# XBee-NewRoute.net
KiCad netlist of a schematic drawn in EAGLE
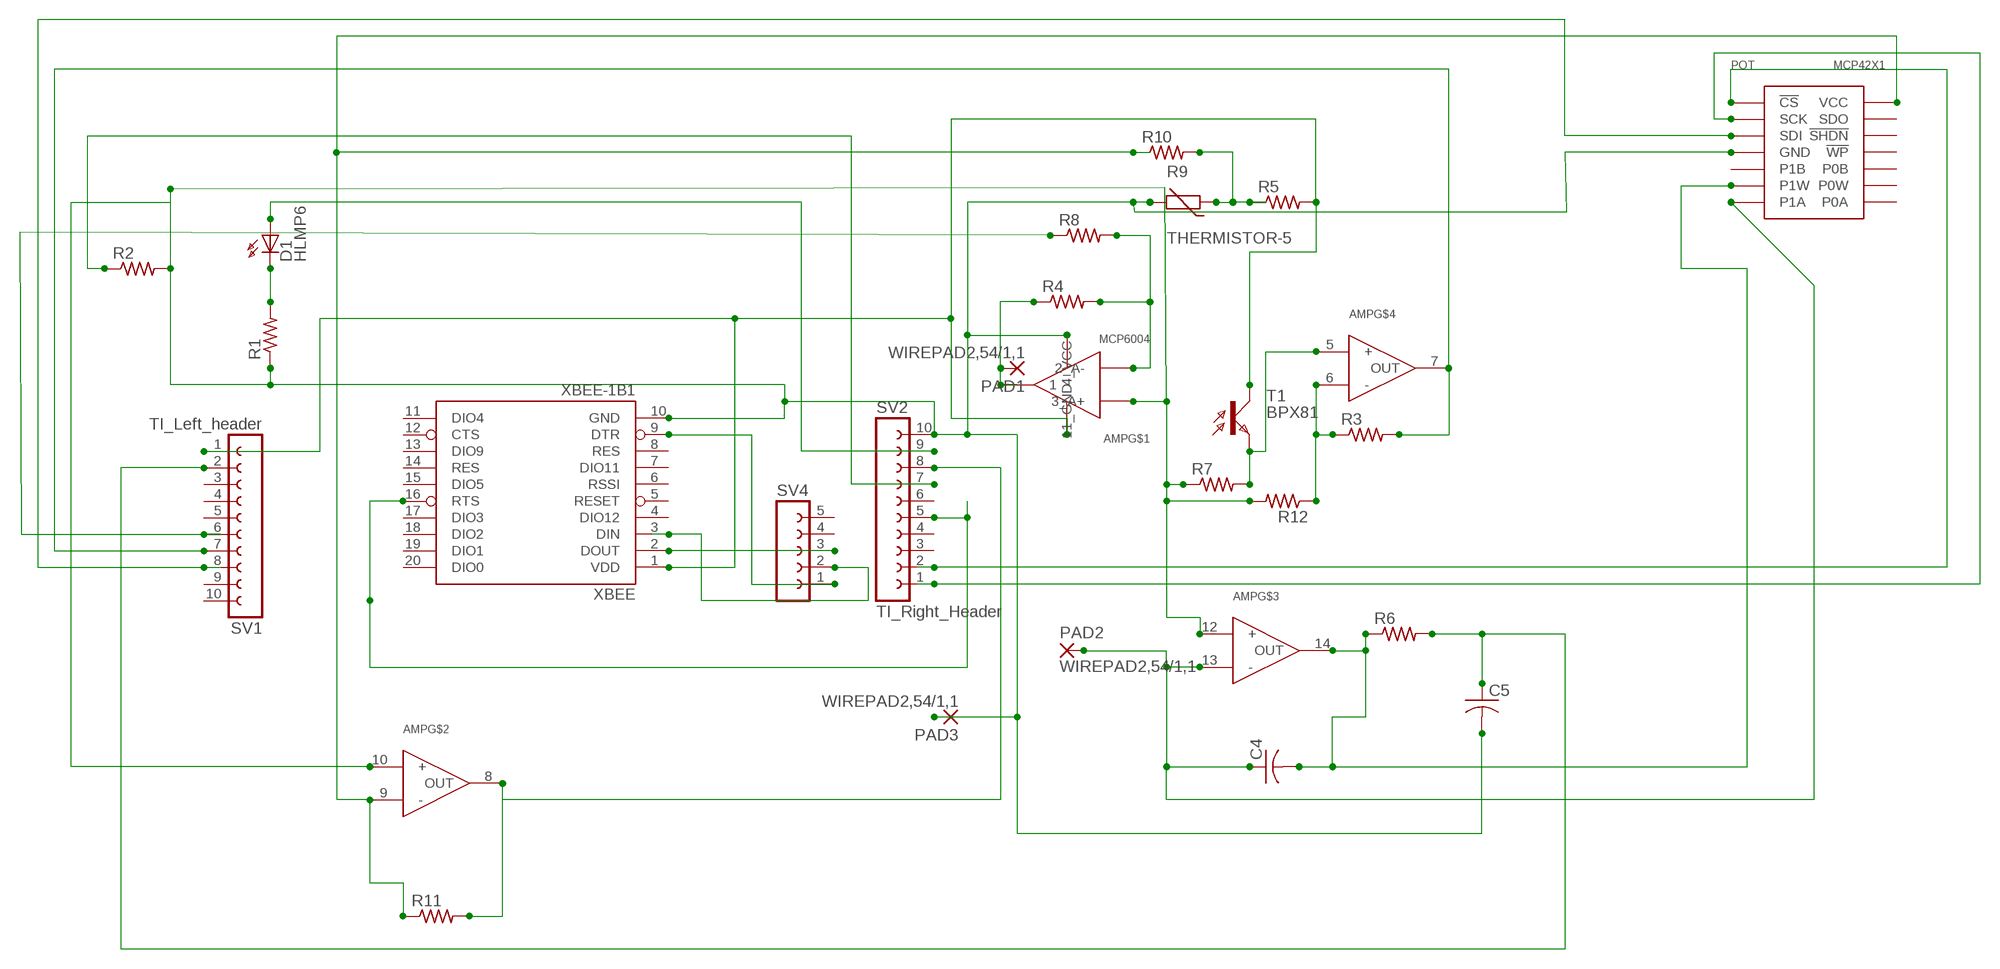
[diagram p0: schematic, sheet 1]

(export (version "E")
  (design (tool "Eeschema 10.0.6"))
  (components
    (comp (ref "AMP")
      (value "MCP6004")
      (footprint "eagle-import:SO014")
      (libsource (lib "eagle-import") (part "MCP6004"))
    )
    (comp (ref "C4")
      (value "C-USC0603")
      (footprint "eagle-import:C0603")
      (libsource (lib "eagle-import") (part "C-USC0603"))
    )
    (comp (ref "C5")
      (value "C-USC0603")
      (footprint "eagle-import:C0603")
      (libsource (lib "eagle-import") (part "C-USC0603"))
    )
    (comp (ref "D1")
      (value "HLMP6")
      (footprint "eagle-import:HLMP6")
      (fields (field (name "MF") "AGILENT TECHNOLOGIES") (field (name "MPN") "HLMP-6500"))
      (libsource (lib "eagle-import") (part "HLMP6"))
    )
    (comp (ref "PAD1")
      (value "WIREPAD2,54/1,1")
      (footprint "eagle-import:2,54_1,1")
      (libsource (lib "eagle-import") (part "WIREPAD2,54/1,1"))
    )
    (comp (ref "PAD2")
      (value "WIREPAD2,54/1,1")
      (footprint "eagle-import:2,54_1,1")
      (libsource (lib "eagle-import") (part "WIREPAD2,54/1,1"))
    )
    (comp (ref "PAD3")
      (value "WIREPAD2,54/1,1")
      (footprint "eagle-import:2,54_1,1")
      (libsource (lib "eagle-import") (part "WIREPAD2,54/1,1"))
    )
    (comp (ref "POT")
      (value "MCP42X1")
      (footprint "eagle-import:SO014")
      (libsource (lib "eagle-import") (part "MCP42X1_DIGITAL_POTSO014"))
    )
    (comp (ref "R1")
      (value "R-US_R0603")
      (footprint "eagle-import:R0603")
      (libsource (lib "eagle-import") (part "R-US_R0603"))
    )
    (comp (ref "R2")
      (value "R-US_R0603")
      (footprint "eagle-import:R0603")
      (libsource (lib "eagle-import") (part "R-US_R0603"))
    )
    (comp (ref "R3")
      (value "R-US_R0603")
      (footprint "eagle-import:R0603")
      (libsource (lib "eagle-import") (part "R-US_R0603"))
    )
    (comp (ref "R4")
      (value "R-US_R0603")
      (footprint "eagle-import:R0603")
      (libsource (lib "eagle-import") (part "R-US_R0603"))
    )
    (comp (ref "R5")
      (value "R-US_R0603")
      (footprint "eagle-import:R0603")
      (libsource (lib "eagle-import") (part "R-US_R0603"))
    )
    (comp (ref "R6")
      (value "R-US_R0603")
      (footprint "eagle-import:R0603")
      (libsource (lib "eagle-import") (part "R-US_R0603"))
    )
    (comp (ref "R7")
      (value "R-US_R0603")
      (footprint "eagle-import:R0603")
      (libsource (lib "eagle-import") (part "R-US_R0603"))
    )
    (comp (ref "R8")
      (value "R-US_R0603")
      (footprint "eagle-import:R0603")
      (libsource (lib "eagle-import") (part "R-US_R0603"))
    )
    (comp (ref "R9")
      (value "THERMISTOR-5")
      (footprint "eagle-import:R-5")
      (libsource (lib "eagle-import") (part "THERMISTOR-5"))
    )
    (comp (ref "R10")
      (value "R-US_R0603")
      (footprint "eagle-import:R0603")
      (libsource (lib "eagle-import") (part "R-US_R0603"))
    )
    (comp (ref "R11")
      (value "R-US_R0603")
      (footprint "eagle-import:R0603")
      (libsource (lib "eagle-import") (part "R-US_R0603"))
    )
    (comp (ref "R12")
      (value "R-US_R0603")
      (footprint "eagle-import:R0603")
      (libsource (lib "eagle-import") (part "R-US_R0603"))
    )
    (comp (ref "SV1")
      (value "TI_Left_header")
      (footprint "eagle-import:FE10")
      (libsource (lib "eagle-import") (part "FE10-1"))
    )
    (comp (ref "SV2")
      (value "TI_Right_Header")
      (footprint "eagle-import:FE10")
      (libsource (lib "eagle-import") (part "FE10-1"))
    )
    (comp (ref "SV4")
      (value "FE05-1")
      (footprint "eagle-import:FE05-1")
      (libsource (lib "eagle-import") (part "FE05-1"))
    )
    (comp (ref "T1")
      (value "BPX81")
      (footprint "eagle-import:BPX81")
      (libsource (lib "eagle-import") (part "BPX81"))
    )
    (comp (ref "XBEE")
      (value "XBEE-1B1")
      (footprint "eagle-import:XBEE-1")
      (libsource (lib "eagle-import") (part "XBEE-1B1"))
    )
  )
  (nets
    (net (code "1") (name "Net-(AMPA-2_A-)") (class "Default")
      (node (ref "AMP") (pin "2") (pinfunction "2_A-_2") (pintype "bidirectional"))
      (node (ref "R4") (pin "2") (pinfunction "2_2") (pintype "passive"))
      (node (ref "R8") (pin "2") (pinfunction "2_2") (pintype "passive"))
    )
    (net (code "2") (name "Net-(AMPA-4_VCC)") (class "Default")
      (node (ref "AMP") (pin "4") (pinfunction "4_VCC_4") (pintype "power_in"))
      (node (ref "R5") (pin "2") (pinfunction "2_2") (pintype "passive"))
      (node (ref "SV1") (pin "1") (pinfunction "1_1") (pintype "passive"))
      (node (ref "T1") (pin "C") (pinfunction "C_C") (pintype "passive"))
      (node (ref "XBEE") (pin "1") (pinfunction "VDD_1") (pintype "power_in"))
    )
    (net (code "3") (name "Net-(AMPA-11_GND)") (class "Default")
      (node (ref "AMP") (pin "10") (pinfunction "+_10") (pintype "bidirectional"))
      (node (ref "AMP") (pin "11") (pinfunction "11_GND_11") (pintype "power_in"))
      (node (ref "AMP") (pin "12") (pinfunction "+_12") (pintype "bidirectional"))
      (node (ref "AMP") (pin "3") (pinfunction "3_A+_3") (pintype "bidirectional"))
      (node (ref "C5") (pin "2") (pinfunction "2_2") (pintype "passive"))
      (node (ref "PAD3") (pin "1") (pinfunction "P_1") (pintype "passive"))
      (node (ref "POT") (pin "P4") (pinfunction "GND_P4") (pintype "bidirectional"))
      (node (ref "R1") (pin "1") (pinfunction "1_1") (pintype "passive"))
      (node (ref "R12") (pin "2") (pinfunction "2_2") (pintype "passive"))
      (node (ref "R2") (pin "2") (pinfunction "2_2") (pintype "passive"))
      (node (ref "R7") (pin "1") (pinfunction "1_1") (pintype "passive"))
      (node (ref "R9") (pin "2") (pinfunction "2_2") (pintype "passive"))
      (node (ref "SV2") (pin "10") (pinfunction "10_10") (pintype "passive"))
      (node (ref "XBEE") (pin "10") (pinfunction "GND_10") (pintype "power_in"))
    )
    (net (code "4") (name "Net-(AMPB--)") (class "Default")
      (node (ref "AMP") (pin "9") (pinfunction "-_9") (pintype "bidirectional"))
      (node (ref "POT") (pin "P14") (pinfunction "VCC_P14") (pintype "bidirectional"))
      (node (ref "R10") (pin "1") (pinfunction "1_1") (pintype "passive"))
      (node (ref "R11") (pin "1") (pinfunction "1_1") (pintype "passive"))
    )
    (net (code "5") (name "Net-(AMPB-OUT)") (class "Default")
      (node (ref "AMP") (pin "8") (pinfunction "OUT_8") (pintype "bidirectional"))
      (node (ref "R11") (pin "2") (pinfunction "2_2") (pintype "passive"))
      (node (ref "SV2") (pin "8") (pinfunction "8_8") (pintype "passive"))
    )
    (net (code "6") (name "Net-(AMPC--)") (class "Default")
      (node (ref "AMP") (pin "13") (pinfunction "-_13") (pintype "bidirectional"))
      (node (ref "C4") (pin "1") (pinfunction "1_1") (pintype "passive"))
      (node (ref "PAD2") (pin "1") (pinfunction "P_1") (pintype "passive"))
      (node (ref "POT") (pin "P7") (pinfunction "P1A_P7") (pintype "bidirectional"))
    )
    (net (code "7") (name "Net-(AMPC-OUT)") (class "Default")
      (node (ref "AMP") (pin "14") (pinfunction "OUT_14") (pintype "bidirectional"))
      (node (ref "C4") (pin "2") (pinfunction "2_2") (pintype "passive"))
      (node (ref "POT") (pin "P6") (pinfunction "P1W_P6") (pintype "bidirectional"))
      (node (ref "R6") (pin "1") (pinfunction "1_1") (pintype "passive"))
    )
    (net (code "8") (name "Net-(AMPD-+)") (class "Default")
      (node (ref "AMP") (pin "5") (pinfunction "+_5") (pintype "bidirectional"))
      (node (ref "R7") (pin "2") (pinfunction "2_2") (pintype "passive"))
      (node (ref "T1") (pin "E") (pinfunction "E_E") (pintype "passive"))
    )
    (net (code "9") (name "Net-(AMPD--)") (class "Default")
      (node (ref "AMP") (pin "6") (pinfunction "-_6") (pintype "bidirectional"))
      (node (ref "R12") (pin "1") (pinfunction "1_1") (pintype "passive"))
      (node (ref "R3") (pin "1") (pinfunction "1_1") (pintype "passive"))
    )
    (net (code "10") (name "Net-(AMPD-OUT)") (class "Default")
      (node (ref "AMP") (pin "7") (pinfunction "OUT_7") (pintype "bidirectional"))
      (node (ref "R3") (pin "2") (pinfunction "2_2") (pintype "passive"))
      (node (ref "SV1") (pin "7") (pinfunction "7_7") (pintype "passive"))
    )
    (net (code "11") (name "Net-(C5-Pad1)") (class "Default")
      (node (ref "C5") (pin "1") (pinfunction "1_1") (pintype "passive"))
      (node (ref "R6") (pin "2") (pinfunction "2_2") (pintype "passive"))
      (node (ref "SV1") (pin "2") (pinfunction "2_2") (pintype "passive"))
    )
    (net (code "12") (name "Net-(D1-PadA)") (class "Default")
      (node (ref "D1") (pin "A") (pinfunction "A_A") (pintype "passive"))
      (node (ref "SV2") (pin "9") (pinfunction "9_9") (pintype "passive"))
    )
    (net (code "13") (name "Net-(D1-PadK)") (class "Default")
      (node (ref "D1") (pin "K") (pinfunction "K_K") (pintype "passive"))
      (node (ref "R1") (pin "2") (pinfunction "2_2") (pintype "passive"))
    )
    (net (code "14") (name "Net-(PAD1-P)") (class "Default")
      (node (ref "AMP") (pin "1") (pinfunction "1_1") (pintype "bidirectional"))
      (node (ref "PAD1") (pin "1") (pinfunction "P_1") (pintype "passive"))
      (node (ref "R4") (pin "1") (pinfunction "1_1") (pintype "passive"))
    )
    (net (code "15") (name "Net-(POT-SCK)") (class "Default")
      (node (ref "POT") (pin "P2") (pinfunction "SCK_P2") (pintype "bidirectional"))
      (node (ref "SV2") (pin "1") (pinfunction "1_1") (pintype "passive"))
    )
    (net (code "16") (name "Net-(POT-SDI)") (class "Default")
      (node (ref "POT") (pin "P3") (pinfunction "SDI_P3") (pintype "bidirectional"))
      (node (ref "SV1") (pin "8") (pinfunction "8_8") (pintype "passive"))
    )
    (net (code "17") (name "Net-(POT-~{CS})") (class "Default")
      (node (ref "POT") (pin "P1") (pinfunction "~{CS}_P1") (pintype "bidirectional"))
      (node (ref "SV2") (pin "2") (pinfunction "2_2") (pintype "passive"))
    )
    (net (code "18") (name "Net-(R2-Pad1)") (class "Default")
      (node (ref "R2") (pin "1") (pinfunction "1_1") (pintype "passive"))
      (node (ref "SV2") (pin "7") (pinfunction "7_7") (pintype "passive"))
    )
    (net (code "19") (name "Net-(R8-Pad1)") (class "Default")
      (node (ref "R8") (pin "1") (pinfunction "1_1") (pintype "passive"))
      (node (ref "SV1") (pin "6") (pinfunction "6_6") (pintype "passive"))
    )
    (net (code "20") (name "Net-(R10-Pad2)") (class "Default")
      (node (ref "R10") (pin "2") (pinfunction "2_2") (pintype "passive"))
      (node (ref "R5") (pin "1") (pinfunction "1_1") (pintype "passive"))
      (node (ref "R9") (pin "1") (pinfunction "1_1") (pintype "passive"))
    )
    (net (code "21") (name "Net-(XBEE-DIN)") (class "Default")
      (node (ref "SV4") (pin "2") (pinfunction "2_2") (pintype "passive"))
      (node (ref "XBEE") (pin "3") (pinfunction "DIN_3") (pintype "input"))
    )
    (net (code "22") (name "Net-(XBEE-DOUT)") (class "Default")
      (node (ref "SV4") (pin "3") (pinfunction "3_3") (pintype "passive"))
      (node (ref "XBEE") (pin "2") (pinfunction "DOUT_2") (pintype "output"))
    )
    (net (code "23") (name "Net-(XBEE-DTR)") (class "Default")
      (node (ref "SV4") (pin "1") (pinfunction "1_1") (pintype "passive"))
      (node (ref "XBEE") (pin "9") (pinfunction "DTR_9") (pintype "bidirectional"))
    )
    (net (code "24") (name "Net-(XBEE-RTS)") (class "Default")
      (node (ref "SV2") (pin "5") (pinfunction "5_5") (pintype "passive"))
      (node (ref "XBEE") (pin "16") (pinfunction "RTS_16") (pintype "input"))
    )
    (net (code "25") (name "unconnected-(POT-P0A-PadP8)") (class "Default")
      (node (ref "POT") (pin "P8") (pinfunction "P0A_P8") (pintype "bidirectional"))
    )
    (net (code "26") (name "unconnected-(POT-P0B-PadP10)") (class "Default")
      (node (ref "POT") (pin "P10") (pinfunction "P0B_P10") (pintype "bidirectional"))
    )
    (net (code "27") (name "unconnected-(POT-P0W-PadP9)") (class "Default")
      (node (ref "POT") (pin "P9") (pinfunction "P0W_P9") (pintype "bidirectional"))
    )
    (net (code "28") (name "unconnected-(POT-P1B-PadP5)") (class "Default")
      (node (ref "POT") (pin "P5") (pinfunction "P1B_P5") (pintype "bidirectional"))
    )
    (net (code "29") (name "unconnected-(POT-SDO-PadP13)") (class "Default")
      (node (ref "POT") (pin "P13") (pinfunction "SDO_P13") (pintype "bidirectional"))
    )
    (net (code "30") (name "unconnected-(POT-~{SHDN}-PadP12)") (class "Default")
      (node (ref "POT") (pin "P12") (pinfunction "~{SHDN}_P12") (pintype "bidirectional"))
    )
    (net (code "31") (name "unconnected-(POT-~{WP}-PadP11)") (class "Default")
      (node (ref "POT") (pin "P11") (pinfunction "~{WP}_P11") (pintype "bidirectional"))
    )
    (net (code "32") (name "unconnected-(SV1-Pad3)") (class "Default")
      (node (ref "SV1") (pin "3") (pinfunction "3_3") (pintype "passive"))
    )
    (net (code "33") (name "unconnected-(SV1-Pad4)") (class "Default")
      (node (ref "SV1") (pin "4") (pinfunction "4_4") (pintype "passive"))
    )
    (net (code "34") (name "unconnected-(SV1-Pad5)") (class "Default")
      (node (ref "SV1") (pin "5") (pinfunction "5_5") (pintype "passive"))
    )
    (net (code "35") (name "unconnected-(SV1-Pad9)") (class "Default")
      (node (ref "SV1") (pin "9") (pinfunction "9_9") (pintype "passive"))
    )
    (net (code "36") (name "unconnected-(SV1-Pad10)") (class "Default")
      (node (ref "SV1") (pin "10") (pinfunction "10_10") (pintype "passive"))
    )
    (net (code "37") (name "unconnected-(SV2-Pad3)") (class "Default")
      (node (ref "SV2") (pin "3") (pinfunction "3_3") (pintype "passive"))
    )
    (net (code "38") (name "unconnected-(SV2-Pad4)") (class "Default")
      (node (ref "SV2") (pin "4") (pinfunction "4_4") (pintype "passive"))
    )
    (net (code "39") (name "unconnected-(SV2-Pad6)") (class "Default")
      (node (ref "SV2") (pin "6") (pinfunction "6_6") (pintype "passive"))
    )
    (net (code "40") (name "unconnected-(SV4-Pad4)") (class "Default")
      (node (ref "SV4") (pin "4") (pinfunction "4_4") (pintype "passive"))
    )
    (net (code "41") (name "unconnected-(SV4-Pad5)") (class "Default")
      (node (ref "SV4") (pin "5") (pinfunction "5_5") (pintype "passive"))
    )
    (net (code "42") (name "unconnected-(XBEE-CTS-Pad12)") (class "Default")
      (node (ref "XBEE") (pin "12") (pinfunction "CTS_12") (pintype "output"))
    )
    (net (code "43") (name "unconnected-(XBEE-DIO0-Pad20)") (class "Default")
      (node (ref "XBEE") (pin "20") (pinfunction "DIO0_20") (pintype "bidirectional"))
    )
    (net (code "44") (name "unconnected-(XBEE-DIO1-Pad19)") (class "Default")
      (node (ref "XBEE") (pin "19") (pinfunction "DIO1_19") (pintype "bidirectional"))
    )
    (net (code "45") (name "unconnected-(XBEE-DIO2-Pad18)") (class "Default")
      (node (ref "XBEE") (pin "18") (pinfunction "DIO2_18") (pintype "bidirectional"))
    )
    (net (code "46") (name "unconnected-(XBEE-DIO3-Pad17)") (class "Default")
      (node (ref "XBEE") (pin "17") (pinfunction "DIO3_17") (pintype "bidirectional"))
    )
    (net (code "47") (name "unconnected-(XBEE-DIO4-Pad11)") (class "Default")
      (node (ref "XBEE") (pin "11") (pinfunction "DIO4_11") (pintype "bidirectional"))
    )
    (net (code "48") (name "unconnected-(XBEE-DIO5-Pad15)") (class "Default")
      (node (ref "XBEE") (pin "15") (pinfunction "DIO5_15") (pintype "bidirectional"))
    )
    (net (code "49") (name "unconnected-(XBEE-DIO9-Pad13)") (class "Default")
      (node (ref "XBEE") (pin "13") (pinfunction "DIO9_13") (pintype "bidirectional"))
    )
    (net (code "50") (name "unconnected-(XBEE-DIO11-Pad7)") (class "Default")
      (node (ref "XBEE") (pin "7") (pinfunction "DIO11_7") (pintype "bidirectional"))
    )
    (net (code "51") (name "unconnected-(XBEE-DIO12-Pad4)") (class "Default")
      (node (ref "XBEE") (pin "4") (pinfunction "DIO12_4") (pintype "bidirectional"))
    )
    (net (code "52") (name "unconnected-(XBEE-RES-Pad8)") (class "Default")
      (node (ref "XBEE") (pin "8") (pinfunction "RES_8") (pintype "bidirectional"))
    )
    (net (code "53") (name "unconnected-(XBEE-RES-Pad14)") (class "Default")
      (node (ref "XBEE") (pin "14") (pinfunction "RES_14") (pintype "bidirectional"))
    )
    (net (code "54") (name "unconnected-(XBEE-RESET-Pad5)") (class "Default")
      (node (ref "XBEE") (pin "5") (pinfunction "RESET_5") (pintype "input"))
    )
    (net (code "55") (name "unconnected-(XBEE-RSSI-Pad6)") (class "Default")
      (node (ref "XBEE") (pin "6") (pinfunction "RSSI_6") (pintype "bidirectional"))
    )
  )
)
